# photodiode-amplifier.net
KiCad netlist of a schematic drawn in Altium Designer
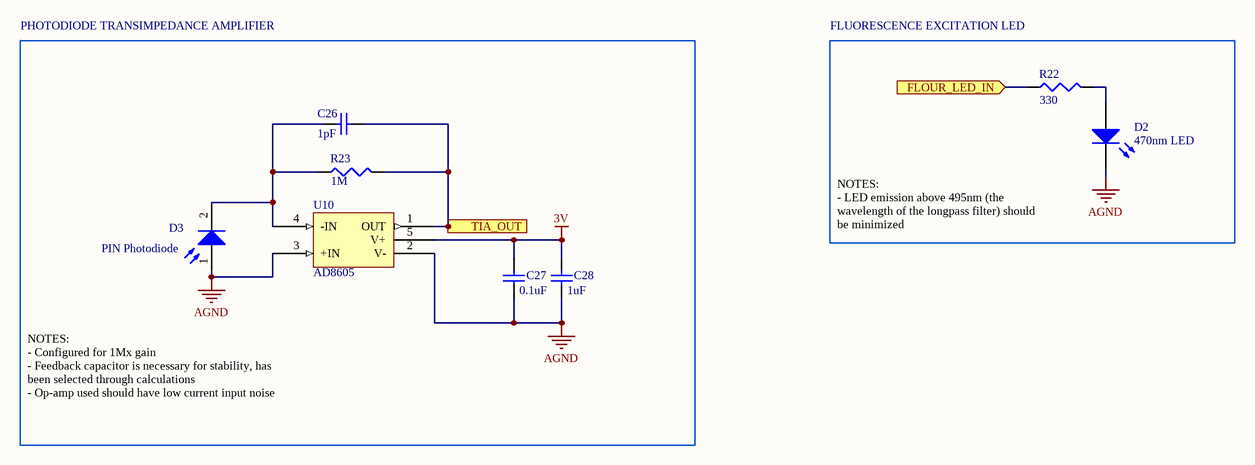
[diagram p0: photodiode-amplifier.SchDoc]

(export (version "E")
  (design (tool "Eeschema 10.0.6"))
  (components
    (comp (ref "C26")
      (value "1pF")
      (footprint "0402")
      (description "Feedback capacitor")
      (fields (field (name "PUBLISHER") "Altium Limited"))
      (libsource (lib "Miscellaneous Devices") (part "Cap Semi"))
    )
    (comp (ref "C27")
      (value "0.1uF")
      (footprint "0402")
      (description "Capacitor (Semiconductor SIM Model)")
      (fields (field (name "PUBLISHER") "Altium Limited"))
      (libsource (lib "Miscellaneous Devices") (part "Cap Semi"))
    )
    (comp (ref "C28")
      (value "1uF")
      (footprint "1608[0603]")
      (description "Capacitor (Semiconductor SIM Model)")
      (fields (field (name "PUBLISHER") "Altium Limited"))
      (libsource (lib "Miscellaneous Devices") (part "Cap Semi"))
    )
    (comp (ref "D2")
      (value "470nm LED")
      (footprint "LB P4SG")
      (description "Typical RED, GREEN, YELLOW, AMBER GaAs LED")
      (fields (field (name "PUBLISHER") "Altium Limited"))
      (libsource (lib "Miscellaneous Devices") (part "LED2"))
    )
    (comp (ref "D3")
      (value "PIN Photodiode")
      (footprint "VBPW34SR")
      (description "Photosensitive Diode")
      (fields (field (name "PUBLISHER") "Altium Limited"))
      (libsource (lib "Miscellaneous Devices") (part "Photo Sen"))
    )
    (comp (ref "R22")
      (value "330")
      (footprint "0402")
      (description "Resistor")
      (fields (field (name "PUBLISHER") "Altium Limited"))
      (libsource (lib "Miscellaneous Devices") (part "Res3"))
    )
    (comp (ref "R23")
      (value "1M")
      (footprint "J1-0603")
      (description "1 MOhm resistor for photodiode gain")
      (fields (field (name "PUBLISHER") "Altium Limited"))
      (libsource (lib "Miscellaneous Devices") (part "Res3"))
    )
    (comp (ref "U10")
      (value "AD8605")
      (footprint "SOP-65P200X125-5N")
      (description "Low noise, precision rail-to-rail op-amp.")
      (libsource (lib "PAY") (part "AD8605"))
    )
  )
  (nets
    (net (code "1") (name "/FLOUR_LED_IN") (class "Default")
      (node (ref "R22") (pin "1") (pinfunction "1_1") (pintype "passive"))
    )
    (net (code "2") (name "/TIA_OUT") (class "Default")
      (node (ref "C26") (pin "2") (pinfunction "2_2") (pintype "passive"))
      (node (ref "R23") (pin "2") (pinfunction "2_2") (pintype "passive"))
      (node (ref "U10") (pin "1") (pinfunction "OUT_1") (pintype "output"))
    )
    (net (code "3") (name "3V") (class "Default")
      (node (ref "C27") (pin "2") (pinfunction "2_2") (pintype "passive"))
      (node (ref "C28") (pin "2") (pinfunction "2_2") (pintype "passive"))
      (node (ref "U10") (pin "5") (pinfunction "V+_5") (pintype "power_in"))
    )
    (net (code "4") (name "AGND") (class "Default")
      (node (ref "C27") (pin "1") (pinfunction "1_1") (pintype "passive"))
      (node (ref "C28") (pin "1") (pinfunction "1_1") (pintype "passive"))
      (node (ref "D2") (pin "2") (pinfunction "K_2") (pintype "passive"))
      (node (ref "D3") (pin "1") (pinfunction "A_1") (pintype "passive"))
      (node (ref "U10") (pin "2") (pinfunction "V-_2") (pintype "power_in"))
      (node (ref "U10") (pin "3") (pinfunction "+IN_3") (pintype "input"))
    )
    (net (code "5") (name "Net-(D2-A)") (class "Default")
      (node (ref "D2") (pin "1") (pinfunction "A_1") (pintype "passive"))
      (node (ref "R22") (pin "2") (pinfunction "2_2") (pintype "passive"))
    )
    (net (code "6") (name "Net-(D3-K)") (class "Default")
      (node (ref "C26") (pin "1") (pinfunction "1_1") (pintype "passive"))
      (node (ref "D3") (pin "2") (pinfunction "K_2") (pintype "passive"))
      (node (ref "R23") (pin "1") (pinfunction "1_1") (pintype "passive"))
      (node (ref "U10") (pin "4") (pinfunction "-IN_4") (pintype "input"))
    )
  )
)
